# 800U-R3N3-Test.net
KiCad netlist of a schematic drawn in Altium Designer
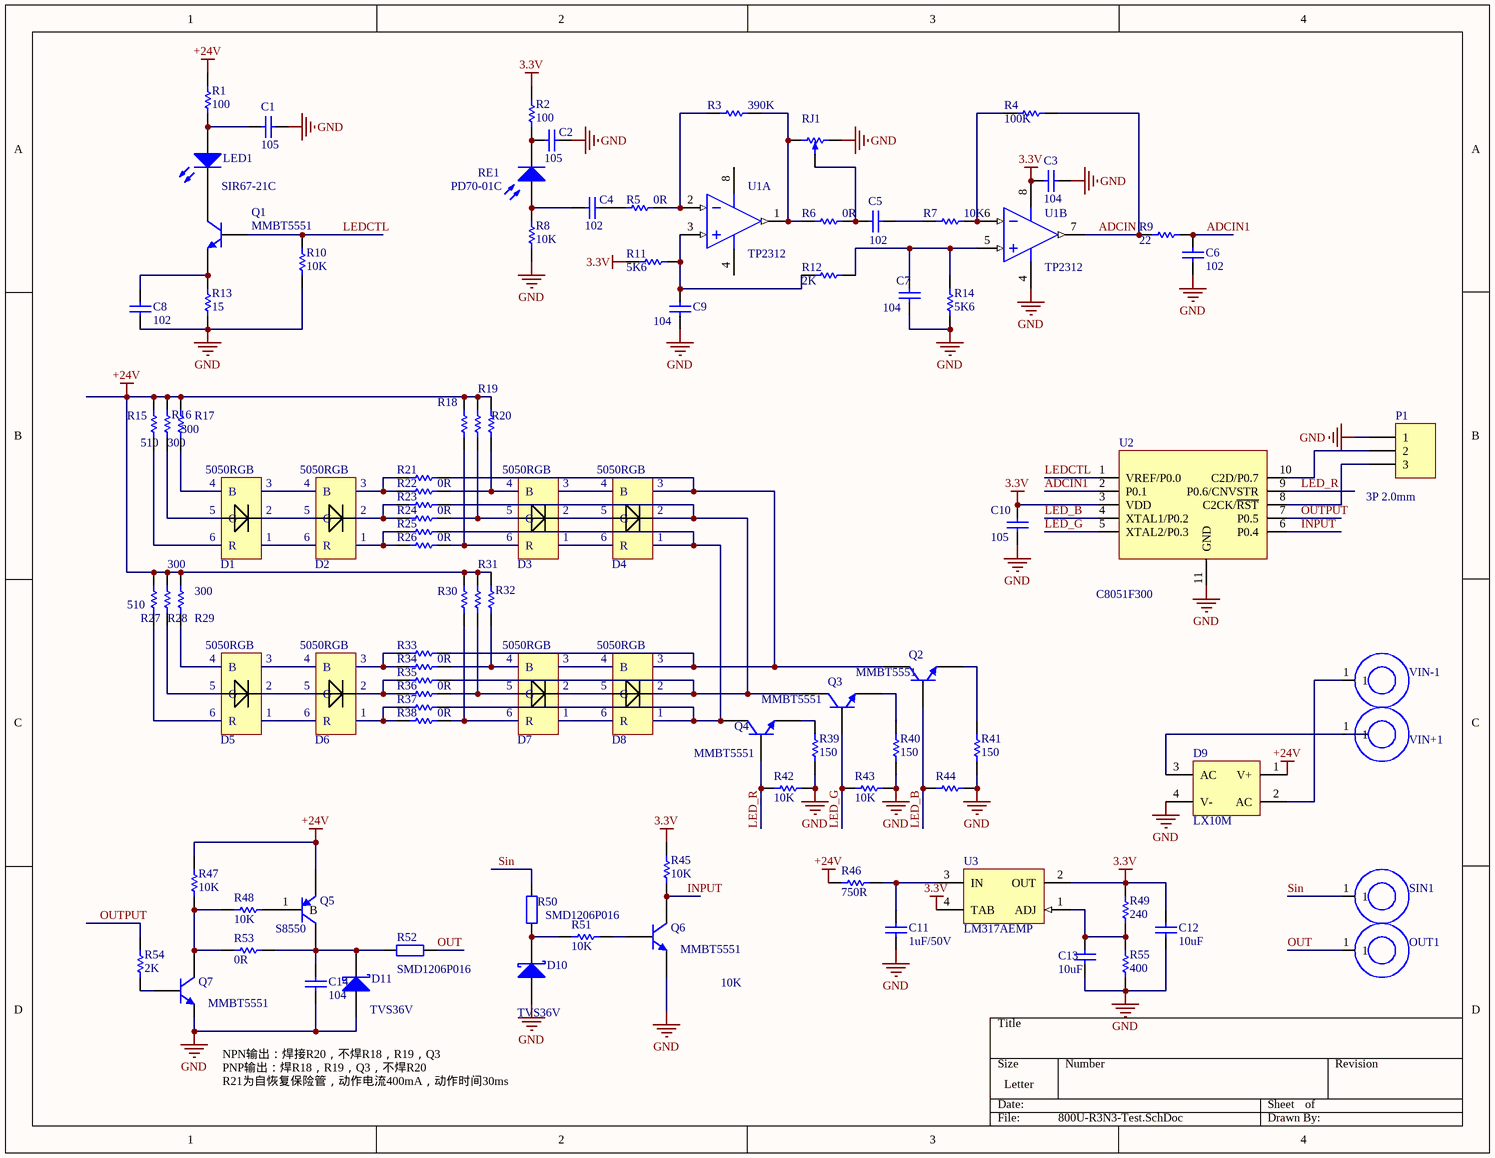
[diagram p0: 800U-R3N3-Test.SchDoc]

(export (version "E")
  (design (tool "Eeschema 10.0.6"))
  (components
    (comp (ref "C1")
      (value "105")
      (footprint "C0805")
      (description "贴片电容")
      (fields (field (name "PUBLISHER") "Altium Limited"))
      (libsource (lib "TMJD1.0") (part "Cap"))
    )
    (comp (ref "C2")
      (value "105")
      (footprint "C0603")
      (description "贴片电容")
      (fields (field (name "PUBLISHER") "Altium Limited"))
      (libsource (lib "TMJD1.0") (part "Cap"))
    )
    (comp (ref "C3")
      (value "104")
      (footprint "C0603")
      (description "贴片电容")
      (fields (field (name "PUBLISHER") "Altium Limited"))
      (libsource (lib "TMJD1.0") (part "Cap"))
    )
    (comp (ref "C4")
      (value "102")
      (footprint "C0603")
      (description "贴片电容")
      (fields (field (name "PUBLISHER") "Altium Limited"))
      (libsource (lib "TMJD1.0") (part "Cap"))
    )
    (comp (ref "C5")
      (value "102")
      (footprint "C0603")
      (description "贴片电容")
      (fields (field (name "PUBLISHER") "Altium Limited"))
      (libsource (lib "TMJD1.0") (part "Cap"))
    )
    (comp (ref "C6")
      (value "102")
      (footprint "C0603")
      (description "贴片电容")
      (fields (field (name "PUBLISHER") "Altium Limited"))
      (libsource (lib "TMJD1.0") (part "Cap"))
    )
    (comp (ref "C7")
      (value "104")
      (footprint "C0603")
      (description "贴片电容")
      (fields (field (name "PUBLISHER") "Altium Limited"))
      (libsource (lib "TMJD1.0") (part "Cap"))
    )
    (comp (ref "C8")
      (value "102")
      (footprint "C0603")
      (description "贴片电容")
      (fields (field (name "PUBLISHER") "Altium Limited"))
      (libsource (lib "TMJD1.0") (part "Cap"))
    )
    (comp (ref "C9")
      (value "104")
      (footprint "C0603")
      (description "贴片电容")
      (fields (field (name "PUBLISHER") "Altium Limited"))
      (libsource (lib "TMJD1.0") (part "Cap"))
    )
    (comp (ref "C10")
      (value "105")
      (footprint "C0603")
      (description "贴片电容")
      (fields (field (name "PUBLISHER") "Altium Limited"))
      (libsource (lib "TMJD1.0") (part "Cap"))
    )
    (comp (ref "C11")
      (value "1uF/50V")
      (footprint "C0603")
      (description "贴片电容")
      (fields (field (name "PUBLISHER") "Altium Limited"))
      (libsource (lib "Miscellaneous Devices") (part "Cap"))
    )
    (comp (ref "C12")
      (value "10uF")
      (footprint "C0603")
      (description "贴片电容")
      (fields (field (name "PUBLISHER") "Altium Limited"))
      (libsource (lib "Miscellaneous Devices") (part "Cap"))
    )
    (comp (ref "C13")
      (value "10uF")
      (footprint "C0603")
      (description "贴片电容")
      (fields (field (name "PUBLISHER") "Altium Limited"))
      (libsource (lib "Miscellaneous Devices") (part "Cap"))
    )
    (comp (ref "C14")
      (value "104")
      (footprint "C0603")
      (description "贴片电容")
      (fields (field (name "PUBLISHER") "Altium Limited"))
      (libsource (lib "TMJD1.0") (part "Cap"))
    )
    (comp (ref "D1")
      (value "5050RGB")
      (footprint "5050RGB")
      (description "贴片RBG发光管")
      (libsource (lib "MODBUS_V1.0") (part "5050RGB"))
    )
    (comp (ref "D2")
      (value "5050RGB")
      (footprint "5050RGB")
      (description "贴片RBG发光管")
      (libsource (lib "MODBUS_V1.0") (part "5050RGB"))
    )
    (comp (ref "D3")
      (value "5050RGB")
      (footprint "5050RGB")
      (description "贴片RBG发光管")
      (libsource (lib "MODBUS_V1.0") (part "5050RGB"))
    )
    (comp (ref "D4")
      (value "5050RGB")
      (footprint "5050RGB")
      (description "贴片RBG发光管")
      (libsource (lib "MODBUS_V1.0") (part "5050RGB"))
    )
    (comp (ref "D5")
      (value "5050RGB")
      (footprint "5050RGB")
      (description "贴片RBG发光管")
      (libsource (lib "MODBUS_V1.0") (part "5050RGB"))
    )
    (comp (ref "D6")
      (value "5050RGB")
      (footprint "5050RGB")
      (description "贴片RBG发光管")
      (libsource (lib "MODBUS_V1.0") (part "5050RGB"))
    )
    (comp (ref "D7")
      (value "5050RGB")
      (footprint "5050RGB")
      (description "贴片RBG发光管")
      (libsource (lib "MODBUS_V1.0") (part "5050RGB"))
    )
    (comp (ref "D8")
      (value "5050RGB")
      (footprint "5050RGB")
      (description "贴片RBG发光管")
      (libsource (lib "MODBUS_V1.0") (part "5050RGB"))
    )
    (comp (ref "D9")
      (value "LX10M")
      (footprint "桥堆 3.8*3.5")
      (description "贴片桥堆")
      (libsource (lib "Miscellaneous Devices") (part "Bridge2"))
    )
    (comp (ref "D10")
      (value "TVS36V")
      (footprint "D1206")
      (description "贴片TVS")
      (fields (field (name "PUBLISHER") "Altium Limited"))
      (libsource (lib "*") (part "D Schottky"))
    )
    (comp (ref "D11")
      (value "TVS36V")
      (footprint "D1206")
      (description "贴片TVS")
      (fields (field (name "PUBLISHER") "Altium Limited"))
      (libsource (lib "*") (part "D Schottky"))
    )
    (comp (ref "LED1")
      (value "SIR67-21C")
      (footprint "LED-3.5X2.8")
      (description "贴片红外发射管")
      (fields (field (name "PUBLISHER") "Altium Limited"))
      (libsource (lib "Miscellaneous Devices") (part "LED0"))
    )
    (comp (ref "OUT1") (value "~") (footprint "HOLE_SMD") (libsource (lib "910U_D24S") (part "HOLE")))
    (comp (ref "P1")
      (value "3P 2.0mm")
      (footprint "PIN3-2.0mm")
      (description "插座")
      (fields (field (name "PUBLISHER") "Altium Limited"))
      (libsource (lib "Miscellaneous Connectors") (part "MHDR1X3"))
    )
    (comp (ref "Q1")
      (value "MMBT5551")
      (footprint "SOT-23")
      (description "贴片NPN三极管")
      (libsource (lib "Miscellaneous Devices") (part "NPN"))
    )
    (comp (ref "Q2")
      (value "MMBT5551")
      (footprint "SOT-23")
      (description "贴片NPN三极管")
      (libsource (lib "Miscellaneous Devices") (part "NPN"))
    )
    (comp (ref "Q3")
      (value "MMBT5551")
      (footprint "SOT-23")
      (description "贴片NPN三极管")
      (libsource (lib "Miscellaneous Devices") (part "NPN"))
    )
    (comp (ref "Q4")
      (value "MMBT5551")
      (footprint "SOT-23")
      (description "贴片NPN三极管")
      (libsource (lib "Miscellaneous Devices") (part "NPN"))
    )
    (comp (ref "Q5")
      (value "S8550")
      (footprint "SOT-23")
      (description "贴片PNP三极管")
      (libsource (lib "MODBUS_V1.0") (part "S8550"))
    )
    (comp (ref "Q6")
      (value "MMBT5551")
      (footprint "SOT-23")
      (description "贴片NPN三极管")
      (libsource (lib "Miscellaneous Devices") (part "NPN"))
    )
    (comp (ref "Q7")
      (value "MMBT5551")
      (footprint "SOT-23")
      (description "NPN三极管")
      (fields (field (name "Comment") "贴片三极管"))
      (libsource (lib "Miscellaneous Devices") (part "NPN"))
    )
    (comp (ref "R1")
      (value "100")
      (footprint "R0805")
      (description "贴片电阻")
      (libsource (lib "Miscellaneous Devices") (part "Res Semi"))
    )
    (comp (ref "R2")
      (value "100")
      (footprint "R0603")
      (description "贴片电阻")
      (libsource (lib "Miscellaneous Devices") (part "Res Semi"))
    )
    (comp (ref "R3")
      (value "390K")
      (footprint "R0603")
      (description "贴片电阻")
      (libsource (lib "Miscellaneous Devices") (part "Res Semi"))
    )
    (comp (ref "R4")
      (value "100K")
      (footprint "R0603")
      (description "贴片电阻")
      (libsource (lib "Miscellaneous Devices") (part "Res Semi"))
    )
    (comp (ref "R5")
      (value "0R")
      (footprint "R0603")
      (description "贴片电阻")
      (libsource (lib "Miscellaneous Devices") (part "Res Semi"))
    )
    (comp (ref "R6")
      (value "0R")
      (footprint "R0603")
      (description "贴片电阻")
      (libsource (lib "Miscellaneous Devices") (part "Res Semi"))
    )
    (comp (ref "R7")
      (value "10K")
      (footprint "R0603")
      (description "贴片电阻")
      (libsource (lib "Miscellaneous Devices") (part "Res Semi"))
    )
    (comp (ref "R8")
      (value "10K")
      (footprint "R0603")
      (description "贴片电阻")
      (libsource (lib "Miscellaneous Devices") (part "Res Semi"))
    )
    (comp (ref "R9")
      (value "22")
      (footprint "R0603")
      (description "贴片电阻")
      (libsource (lib "Miscellaneous Devices") (part "Res Semi"))
    )
    (comp (ref "R10")
      (value "10K")
      (footprint "R0603")
      (description "贴片电阻")
      (libsource (lib "Miscellaneous Devices") (part "Res Semi"))
    )
    (comp (ref "R11")
      (value "5K6")
      (footprint "R0603")
      (description "贴片电阻")
      (libsource (lib "Miscellaneous Devices") (part "Res Semi"))
    )
    (comp (ref "R12")
      (value "2K")
      (footprint "R0603")
      (description "贴片电阻")
      (libsource (lib "Miscellaneous Devices") (part "Res Semi"))
    )
    (comp (ref "R13")
      (value "15")
      (footprint "R0805")
      (description "贴片电阻")
      (libsource (lib "Miscellaneous Devices") (part "Res Semi"))
    )
    (comp (ref "R14")
      (value "5K6")
      (footprint "R0603")
      (description "贴片电阻")
      (libsource (lib "Miscellaneous Devices") (part "Res Semi"))
    )
    (comp (ref "R15")
      (value "510")
      (footprint "2010")
      (description "贴片电阻")
      (libsource (lib "Miscellaneous Devices") (part "Res Semi"))
    )
    (comp (ref "R16")
      (value "300")
      (footprint "2010")
      (description "贴片电阻")
      (libsource (lib "Miscellaneous Devices") (part "Res Semi"))
    )
    (comp (ref "R17")
      (value "300")
      (footprint "2010")
      (description "贴片电阻")
      (libsource (lib "Miscellaneous Devices") (part "Res Semi"))
    )
    (comp (ref "R18")
      (value "~")
      (footprint "2010")
      (description "贴片电阻")
      (libsource (lib "Miscellaneous Devices") (part "Res Semi"))
    )
    (comp (ref "R19")
      (value "~")
      (footprint "2010")
      (description "贴片电阻")
      (libsource (lib "Miscellaneous Devices") (part "Res Semi"))
    )
    (comp (ref "R20")
      (value "~")
      (footprint "2010")
      (description "贴片电阻")
      (libsource (lib "Miscellaneous Devices") (part "Res Semi"))
    )
    (comp (ref "R21")
      (value "~")
      (footprint "R0603")
      (description "贴片电阻")
      (libsource (lib "Miscellaneous Devices") (part "Res Semi"))
    )
    (comp (ref "R22")
      (value "0R")
      (footprint "R0603")
      (description "贴片电阻")
      (libsource (lib "Miscellaneous Devices") (part "Res Semi"))
    )
    (comp (ref "R23")
      (value "~")
      (footprint "R0603")
      (description "贴片电阻")
      (libsource (lib "Miscellaneous Devices") (part "Res Semi"))
    )
    (comp (ref "R24")
      (value "0R")
      (footprint "R0603")
      (description "贴片电阻")
      (libsource (lib "Miscellaneous Devices") (part "Res Semi"))
    )
    (comp (ref "R25")
      (value "~")
      (footprint "R0603")
      (description "贴片电阻")
      (libsource (lib "Miscellaneous Devices") (part "Res Semi"))
    )
    (comp (ref "R26")
      (value "0R")
      (footprint "R0603")
      (description "贴片电阻")
      (libsource (lib "Miscellaneous Devices") (part "Res Semi"))
    )
    (comp (ref "R27")
      (value "510")
      (footprint "2010")
      (description "贴片电阻")
      (libsource (lib "Miscellaneous Devices") (part "Res Semi"))
    )
    (comp (ref "R28")
      (value "300")
      (footprint "2010")
      (description "贴片电阻")
      (libsource (lib "Miscellaneous Devices") (part "Res Semi"))
    )
    (comp (ref "R29")
      (value "300")
      (footprint "2010")
      (description "贴片电阻")
      (libsource (lib "Miscellaneous Devices") (part "Res Semi"))
    )
    (comp (ref "R30")
      (value "~")
      (footprint "2010")
      (description "贴片电阻")
      (libsource (lib "Miscellaneous Devices") (part "Res Semi"))
    )
    (comp (ref "R31")
      (value "~")
      (footprint "2010")
      (description "贴片电阻")
      (libsource (lib "Miscellaneous Devices") (part "Res Semi"))
    )
    (comp (ref "R32")
      (value "~")
      (footprint "2010")
      (description "贴片电阻")
      (libsource (lib "Miscellaneous Devices") (part "Res Semi"))
    )
    (comp (ref "R33")
      (value "~")
      (footprint "R0603")
      (description "贴片电阻")
      (libsource (lib "Miscellaneous Devices") (part "Res Semi"))
    )
    (comp (ref "R34")
      (value "0R")
      (footprint "R0603")
      (description "贴片电阻")
      (libsource (lib "Miscellaneous Devices") (part "Res Semi"))
    )
    (comp (ref "R35")
      (value "~")
      (footprint "R0603")
      (description "贴片电阻")
      (libsource (lib "Miscellaneous Devices") (part "Res Semi"))
    )
    (comp (ref "R36")
      (value "0R")
      (footprint "R0603")
      (description "贴片电阻")
      (libsource (lib "Miscellaneous Devices") (part "Res Semi"))
    )
    (comp (ref "R37")
      (value "~")
      (footprint "R0603")
      (description "贴片电阻")
      (libsource (lib "Miscellaneous Devices") (part "Res Semi"))
    )
    (comp (ref "R38")
      (value "0R")
      (footprint "R0603")
      (description "贴片电阻")
      (libsource (lib "Miscellaneous Devices") (part "Res Semi"))
    )
    (comp (ref "R39")
      (value "150")
      (footprint "2010")
      (description "贴片电阻")
      (libsource (lib "Miscellaneous Devices") (part "Res Semi"))
    )
    (comp (ref "R40")
      (value "150")
      (footprint "2010")
      (description "贴片电阻")
      (libsource (lib "Miscellaneous Devices") (part "Res Semi"))
    )
    (comp (ref "R41")
      (value "150")
      (footprint "2010")
      (description "贴片电阻")
      (libsource (lib "Miscellaneous Devices") (part "Res Semi"))
    )
    (comp (ref "R42")
      (value "10K")
      (footprint "R0603")
      (description "贴片电阻")
      (libsource (lib "Miscellaneous Devices") (part "Res Semi"))
    )
    (comp (ref "R43")
      (value "10K")
      (footprint "R0603")
      (description "贴片电阻")
      (libsource (lib "Miscellaneous Devices") (part "Res Semi"))
    )
    (comp (ref "R44")
      (value "10K")
      (footprint "R0603")
      (description "贴片电阻")
      (libsource (lib "Miscellaneous Devices") (part "Res Semi"))
    )
    (comp (ref "R45")
      (value "10K")
      (footprint "R0603")
      (description "贴片电阻")
      (libsource (lib "Miscellaneous Devices") (part "Res Semi"))
    )
    (comp (ref "R46")
      (value "750R")
      (footprint "2010")
      (description "贴片电阻")
      (libsource (lib "Miscellaneous Devices") (part "Res Semi"))
    )
    (comp (ref "R47")
      (value "10K")
      (footprint "R0603")
      (description "贴片电阻")
      (libsource (lib "Miscellaneous Devices") (part "Res Semi"))
    )
    (comp (ref "R48")
      (value "10K")
      (footprint "R0603")
      (description "贴片电阻")
      (libsource (lib "Miscellaneous Devices") (part "Res Semi"))
    )
    (comp (ref "R49")
      (value "240")
      (footprint "R0603")
      (description "贴片电阻")
      (libsource (lib "Miscellaneous Devices") (part "Res Semi"))
    )
    (comp (ref "R50")
      (value "SMD1206P016")
      (footprint "1206")
      (description "贴片过流保护")
      (fields (field (name "PUBLISHER") "Altium Limited"))
      (libsource (lib "Miscellaneous Devices") (part "Res2"))
    )
    (comp (ref "R51")
      (value "10K")
      (footprint "R0603")
      (description "贴片电阻")
      (libsource (lib "Miscellaneous Devices") (part "Res Semi"))
    )
    (comp (ref "R52")
      (value "SMD1206P016")
      (footprint "1206")
      (description "贴片过流保护")
      (fields (field (name "PUBLISHER") "Altium Limited"))
      (libsource (lib "") (part "Res2_1"))
    )
    (comp (ref "R53")
      (value "0R")
      (footprint "R0603")
      (description "贴片电阻")
      (libsource (lib "Miscellaneous Devices") (part "Res Semi"))
    )
    (comp (ref "R54")
      (value "2K")
      (footprint "R0603")
      (description "贴片电阻")
      (libsource (lib "Miscellaneous Devices") (part "Res Semi"))
    )
    (comp (ref "R55")
      (value "400")
      (footprint "R0603")
      (description "贴片电阻")
      (libsource (lib "Miscellaneous Devices") (part "Res Semi"))
    )
    (comp (ref "RE1")
      (value "PD70-01C")
      (footprint "LED-1210")
      (description "贴片接收管")
      (fields (field (name "PUBLISHER") "Altium Limited"))
      (libsource (lib "Miscellaneous Devices") (part "Photo Sen"))
    )
    (comp (ref "RJ1")
      (value "~")
      (footprint "POT4MM-2")
      (description "贴片可调电阻")
      (fields (field (name "PUBLISHER") "Altium Limited"))
      (libsource (lib "Miscellaneous Devices") (part "RPot SM"))
    )
    (comp (ref "SIN1") (value "~") (footprint "HOLE_SMD") (libsource (lib "910U_D24S") (part "HOLE")))
    (comp (ref "U1")
      (value "TP2312")
      (footprint "SO-8")
      (description "贴片芯片")
      (fields (field (name "PUBLISHER") "Altium Limited"))
      (libsource (lib "Motorola Amplifier Audio Amplifier") (part "LM833D"))
    )
    (comp (ref "U2")
      (value "C8051F300")
      (footprint "IC3-3-14P")
      (description "贴片芯片")
      (libsource (lib "集成块") (part "PIC16C505"))
    )
    (comp (ref "U3")
      (value "LM317AEMP")
      (footprint "MP04A_N")
      (description "贴片芯片")
      (fields
        (field (name "MANUFACTURER") "National Semiconductor")
        (field (name "DIGIKEYPARTNUMBER") "LM317AEMPCT-ND")
        (field (name "PUBLISHER") "Altium Limited")
      )
      (libsource (lib "NSC LDO") (part "LM317AEMP"))
    )
    (comp (ref "VIN+1") (value "~") (footprint "HOLE_SMD") (libsource (lib "910U_D24S") (part "HOLE")))
    (comp (ref "VIN-1") (value "~") (footprint "HOLE_SMD") (libsource (lib "910U_D24S") (part "HOLE")))
  )
  (nets
    (net (code "1") (name "+24V") (class "Default")
      (node (ref "D9") (pin "1") (pinfunction "V+_1") (pintype "passive"))
      (node (ref "Q5") (pin "2") (pinfunction "E_2") (pintype "passive"))
      (node (ref "R1") (pin "2") (pinfunction "2_2") (pintype "passive"))
      (node (ref "R15") (pin "1") (pinfunction "1_1") (pintype "passive"))
      (node (ref "R16") (pin "1") (pinfunction "1_1") (pintype "passive"))
      (node (ref "R17") (pin "1") (pinfunction "1_1") (pintype "passive"))
      (node (ref "R18") (pin "1") (pinfunction "1_1") (pintype "passive"))
      (node (ref "R19") (pin "1") (pinfunction "1_1") (pintype "passive"))
      (node (ref "R20") (pin "1") (pinfunction "1_1") (pintype "passive"))
      (node (ref "R27") (pin "1") (pinfunction "1_1") (pintype "passive"))
      (node (ref "R28") (pin "1") (pinfunction "1_1") (pintype "passive"))
      (node (ref "R29") (pin "1") (pinfunction "1_1") (pintype "passive"))
      (node (ref "R30") (pin "1") (pinfunction "1_1") (pintype "passive"))
      (node (ref "R31") (pin "1") (pinfunction "1_1") (pintype "passive"))
      (node (ref "R32") (pin "1") (pinfunction "1_1") (pintype "passive"))
      (node (ref "R46") (pin "1") (pinfunction "1_1") (pintype "passive"))
      (node (ref "R47") (pin "2") (pinfunction "2_2") (pintype "passive"))
    )
    (net (code "2") (name "/ADCIN") (class "Default")
      (node (ref "R4") (pin "2") (pinfunction "2_2") (pintype "passive"))
      (node (ref "R9") (pin "1") (pinfunction "1_1") (pintype "passive"))
      (node (ref "U1") (pin "7") (pinfunction "OUT_7") (pintype "output"))
    )
    (net (code "3") (name "/ADCIN1") (class "Default")
      (node (ref "C6") (pin "2") (pinfunction "2_2") (pintype "passive"))
      (node (ref "R9") (pin "2") (pinfunction "2_2") (pintype "passive"))
      (node (ref "U2") (pin "2") (pinfunction "P0.1_2") (pintype "passive"))
    )
    (net (code "4") (name "/INPUT") (class "Default")
      (node (ref "Q6") (pin "3") (pinfunction "C_3") (pintype "passive"))
      (node (ref "R45") (pin "1") (pinfunction "1_1") (pintype "passive"))
      (node (ref "U2") (pin "6") (pinfunction "P0.4_6") (pintype "passive"))
    )
    (net (code "5") (name "/LEDCTL") (class "Default")
      (node (ref "Q1") (pin "1") (pinfunction "B_1") (pintype "passive"))
      (node (ref "R10") (pin "2") (pinfunction "2_2") (pintype "passive"))
      (node (ref "U2") (pin "1") (pinfunction "VREF/P0.0_1") (pintype "passive"))
    )
    (net (code "6") (name "/LED_B") (class "Default")
      (node (ref "Q2") (pin "1") (pinfunction "B_1") (pintype "passive"))
      (node (ref "R44") (pin "1") (pinfunction "1_1") (pintype "passive"))
      (node (ref "U2") (pin "4") (pinfunction "XTAL1/P0.2_4") (pintype "passive"))
    )
    (net (code "7") (name "/LED_G") (class "Default")
      (node (ref "Q3") (pin "1") (pinfunction "B_1") (pintype "passive"))
      (node (ref "R43") (pin "1") (pinfunction "1_1") (pintype "passive"))
      (node (ref "U2") (pin "5") (pinfunction "XTAL2/P0.3_5") (pintype "passive"))
    )
    (net (code "8") (name "/LED_R") (class "Default")
      (node (ref "Q4") (pin "1") (pinfunction "B_1") (pintype "passive"))
      (node (ref "R42") (pin "1") (pinfunction "1_1") (pintype "passive"))
      (node (ref "U2") (pin "9") (pinfunction "P0.6/CNVSTR_9") (pintype "passive"))
    )
    (net (code "9") (name "/OUT") (class "Default")
      (node (ref "OUT1") (pin "1") (pinfunction "1_1") (pintype "passive"))
      (node (ref "R52") (pin "2") (pinfunction "2_2") (pintype "passive"))
    )
    (net (code "10") (name "/OUTPUT") (class "Default")
      (node (ref "R54") (pin "2") (pinfunction "2_2") (pintype "passive"))
      (node (ref "U2") (pin "7") (pinfunction "P0.5_7") (pintype "passive"))
    )
    (net (code "11") (name "/Sin") (class "Default")
      (node (ref "R50") (pin "2") (pinfunction "2_2") (pintype "passive"))
      (node (ref "SIN1") (pin "1") (pinfunction "1_1") (pintype "passive"))
    )
    (net (code "12") (name "3.3V") (class "Default")
      (node (ref "C10") (pin "1") (pinfunction "1_1") (pintype "passive"))
      (node (ref "C12") (pin "1") (pinfunction "1_1") (pintype "passive"))
      (node (ref "C3") (pin "1") (pinfunction "1_1") (pintype "passive"))
      (node (ref "R11") (pin "1") (pinfunction "1_1") (pintype "passive"))
      (node (ref "R2") (pin "2") (pinfunction "2_2") (pintype "passive"))
      (node (ref "R45") (pin "2") (pinfunction "2_2") (pintype "passive"))
      (node (ref "R49") (pin "2") (pinfunction "2_2") (pintype "passive"))
      (node (ref "U1") (pin "8") (pinfunction "VCC_8") (pintype "power_in"))
      (node (ref "U2") (pin "3") (pinfunction "VDD_3") (pintype "passive"))
      (node (ref "U3") (pin "2") (pinfunction "OUT_2") (pintype "power_in"))
      (node (ref "U3") (pin "4") (pinfunction "TAB_4") (pintype "power_in"))
    )
    (net (code "13") (name "GND") (class "Default")
      (node (ref "C1") (pin "2") (pinfunction "2_2") (pintype "passive"))
      (node (ref "C10") (pin "2") (pinfunction "2_2") (pintype "passive"))
      (node (ref "C11") (pin "2") (pinfunction "2_2") (pintype "passive"))
      (node (ref "C12") (pin "2") (pinfunction "2_2") (pintype "passive"))
      (node (ref "C13") (pin "2") (pinfunction "2_2") (pintype "passive"))
      (node (ref "C14") (pin "2") (pinfunction "2_2") (pintype "passive"))
      (node (ref "C2") (pin "2") (pinfunction "2_2") (pintype "passive"))
      (node (ref "C3") (pin "2") (pinfunction "2_2") (pintype "passive"))
      (node (ref "C6") (pin "1") (pinfunction "1_1") (pintype "passive"))
      (node (ref "C7") (pin "2") (pinfunction "2_2") (pintype "passive"))
      (node (ref "C8") (pin "2") (pinfunction "2_2") (pintype "passive"))
      (node (ref "C9") (pin "2") (pinfunction "2_2") (pintype "passive"))
      (node (ref "D10") (pin "1") (pinfunction "A_1") (pintype "passive"))
      (node (ref "D11") (pin "1") (pinfunction "A_1") (pintype "passive"))
      (node (ref "D9") (pin "4") (pinfunction "V-_4") (pintype "passive"))
      (node (ref "P1") (pin "1") (pinfunction "1_1") (pintype "passive"))
      (node (ref "Q6") (pin "2") (pinfunction "E_2") (pintype "passive"))
      (node (ref "Q7") (pin "2") (pinfunction "E_2") (pintype "passive"))
      (node (ref "R10") (pin "1") (pinfunction "1_1") (pintype "passive"))
      (node (ref "R13") (pin "1") (pinfunction "1_1") (pintype "passive"))
      (node (ref "R14") (pin "1") (pinfunction "1_1") (pintype "passive"))
      (node (ref "R39") (pin "2") (pinfunction "2_2") (pintype "passive"))
      (node (ref "R40") (pin "2") (pinfunction "2_2") (pintype "passive"))
      (node (ref "R41") (pin "2") (pinfunction "2_2") (pintype "passive"))
      (node (ref "R42") (pin "2") (pinfunction "2_2") (pintype "passive"))
      (node (ref "R43") (pin "2") (pinfunction "2_2") (pintype "passive"))
      (node (ref "R44") (pin "2") (pinfunction "2_2") (pintype "passive"))
      (node (ref "R55") (pin "1") (pinfunction "1_1") (pintype "passive"))
      (node (ref "R8") (pin "1") (pinfunction "1_1") (pintype "passive"))
      (node (ref "RJ1") (pin "CW") (pinfunction "+_CW") (pintype "passive"))
      (node (ref "U1") (pin "4") (pinfunction "VEE_4") (pintype "power_in"))
      (node (ref "U2") (pin "11") (pinfunction "GND_11") (pintype "passive"))
    )
    (net (code "14") (name "Net-(C4-Pad2)") (class "Default")
      (node (ref "C4") (pin "2") (pinfunction "2_2") (pintype "passive"))
      (node (ref "R5") (pin "1") (pinfunction "1_1") (pintype "passive"))
    )
    (net (code "15") (name "Net-(C5-Pad1)") (class "Default")
      (node (ref "C5") (pin "1") (pinfunction "1_1") (pintype "passive"))
      (node (ref "R6") (pin "2") (pinfunction "2_2") (pintype "passive"))
      (node (ref "RJ1") (pin "W") (pinfunction "W_W") (pintype "passive"))
    )
    (net (code "16") (name "Net-(C5-Pad2)") (class "Default")
      (node (ref "C5") (pin "2") (pinfunction "2_2") (pintype "passive"))
      (node (ref "R7") (pin "1") (pinfunction "1_1") (pintype "passive"))
    )
    (net (code "17") (name "Net-(D1-B)") (class "Default")
      (node (ref "D1") (pin "4") (pinfunction "B_4") (pintype "passive"))
      (node (ref "R17") (pin "2") (pinfunction "2_2") (pintype "passive"))
    )
    (net (code "18") (name "Net-(D1-G)") (class "Default")
      (node (ref "D1") (pin "5") (pinfunction "G_5") (pintype "passive"))
      (node (ref "R16") (pin "2") (pinfunction "2_2") (pintype "passive"))
    )
    (net (code "19") (name "Net-(D1-R)") (class "Default")
      (node (ref "D1") (pin "6") (pinfunction "R_6") (pintype "passive"))
      (node (ref "R15") (pin "2") (pinfunction "2_2") (pintype "passive"))
    )
    (net (code "20") (name "Net-(D2-B)") (class "Default")
      (node (ref "D1") (pin "3") (pintype "passive"))
      (node (ref "D2") (pin "4") (pinfunction "B_4") (pintype "passive"))
    )
    (net (code "21") (name "Net-(D2-G)") (class "Default")
      (node (ref "D1") (pin "2") (pintype "passive"))
      (node (ref "D2") (pin "5") (pinfunction "G_5") (pintype "passive"))
    )
    (net (code "22") (name "Net-(D2-Pad1)") (class "Default")
      (node (ref "D2") (pin "1") (pintype "passive"))
      (node (ref "R25") (pin "1") (pinfunction "1_1") (pintype "passive"))
      (node (ref "R26") (pin "1") (pinfunction "1_1") (pintype "passive"))
    )
    (net (code "23") (name "Net-(D2-Pad2)") (class "Default")
      (node (ref "D2") (pin "2") (pintype "passive"))
      (node (ref "R23") (pin "1") (pinfunction "1_1") (pintype "passive"))
      (node (ref "R24") (pin "1") (pinfunction "1_1") (pintype "passive"))
    )
    (net (code "24") (name "Net-(D2-Pad3)") (class "Default")
      (node (ref "D2") (pin "3") (pintype "passive"))
      (node (ref "R21") (pin "1") (pinfunction "1_1") (pintype "passive"))
      (node (ref "R22") (pin "1") (pinfunction "1_1") (pintype "passive"))
    )
    (net (code "25") (name "Net-(D2-R)") (class "Default")
      (node (ref "D1") (pin "1") (pintype "passive"))
      (node (ref "D2") (pin "6") (pinfunction "R_6") (pintype "passive"))
    )
    (net (code "26") (name "Net-(D3-B)") (class "Default")
      (node (ref "D3") (pin "4") (pinfunction "B_4") (pintype "passive"))
      (node (ref "R20") (pin "2") (pinfunction "2_2") (pintype "passive"))
      (node (ref "R22") (pin "2") (pinfunction "2_2") (pintype "passive"))
    )
    (net (code "27") (name "Net-(D3-G)") (class "Default")
      (node (ref "D3") (pin "5") (pinfunction "G_5") (pintype "passive"))
      (node (ref "R19") (pin "2") (pinfunction "2_2") (pintype "passive"))
      (node (ref "R24") (pin "2") (pinfunction "2_2") (pintype "passive"))
    )
    (net (code "28") (name "Net-(D3-R)") (class "Default")
      (node (ref "D3") (pin "6") (pinfunction "R_6") (pintype "passive"))
      (node (ref "R18") (pin "2") (pinfunction "2_2") (pintype "passive"))
      (node (ref "R26") (pin "2") (pinfunction "2_2") (pintype "passive"))
    )
    (net (code "29") (name "Net-(D4-B)") (class "Default")
      (node (ref "D3") (pin "3") (pintype "passive"))
      (node (ref "D4") (pin "4") (pinfunction "B_4") (pintype "passive"))
    )
    (net (code "30") (name "Net-(D4-G)") (class "Default")
      (node (ref "D3") (pin "2") (pintype "passive"))
      (node (ref "D4") (pin "5") (pinfunction "G_5") (pintype "passive"))
    )
    (net (code "31") (name "Net-(D4-R)") (class "Default")
      (node (ref "D3") (pin "1") (pintype "passive"))
      (node (ref "D4") (pin "6") (pinfunction "R_6") (pintype "passive"))
    )
    (net (code "32") (name "Net-(D5-B)") (class "Default")
      (node (ref "D5") (pin "4") (pinfunction "B_4") (pintype "passive"))
      (node (ref "R29") (pin "2") (pinfunction "2_2") (pintype "passive"))
    )
    (net (code "33") (name "Net-(D5-G)") (class "Default")
      (node (ref "D5") (pin "5") (pinfunction "G_5") (pintype "passive"))
      (node (ref "R28") (pin "2") (pinfunction "2_2") (pintype "passive"))
    )
    (net (code "34") (name "Net-(D5-R)") (class "Default")
      (node (ref "D5") (pin "6") (pinfunction "R_6") (pintype "passive"))
      (node (ref "R27") (pin "2") (pinfunction "2_2") (pintype "passive"))
    )
    (net (code "35") (name "Net-(D6-B)") (class "Default")
      (node (ref "D5") (pin "3") (pintype "passive"))
      (node (ref "D6") (pin "4") (pinfunction "B_4") (pintype "passive"))
    )
    (net (code "36") (name "Net-(D6-G)") (class "Default")
      (node (ref "D5") (pin "2") (pintype "passive"))
      (node (ref "D6") (pin "5") (pinfunction "G_5") (pintype "passive"))
    )
    (net (code "37") (name "Net-(D6-Pad1)") (class "Default")
      (node (ref "D6") (pin "1") (pintype "passive"))
      (node (ref "R37") (pin "1") (pinfunction "1_1") (pintype "passive"))
      (node (ref "R38") (pin "1") (pinfunction "1_1") (pintype "passive"))
    )
    (net (code "38") (name "Net-(D6-Pad2)") (class "Default")
      (node (ref "D6") (pin "2") (pintype "passive"))
      (node (ref "R35") (pin "1") (pinfunction "1_1") (pintype "passive"))
      (node (ref "R36") (pin "1") (pinfunction "1_1") (pintype "passive"))
    )
    (net (code "39") (name "Net-(D6-Pad3)") (class "Default")
      (node (ref "D6") (pin "3") (pintype "passive"))
      (node (ref "R33") (pin "1") (pinfunction "1_1") (pintype "passive"))
      (node (ref "R34") (pin "1") (pinfunction "1_1") (pintype "passive"))
    )
    (net (code "40") (name "Net-(D6-R)") (class "Default")
      (node (ref "D5") (pin "1") (pintype "passive"))
      (node (ref "D6") (pin "6") (pinfunction "R_6") (pintype "passive"))
    )
    (net (code "41") (name "Net-(D7-B)") (class "Default")
      (node (ref "D7") (pin "4") (pinfunction "B_4") (pintype "passive"))
      (node (ref "R32") (pin "2") (pinfunction "2_2") (pintype "passive"))
      (node (ref "R34") (pin "2") (pinfunction "2_2") (pintype "passive"))
    )
    (net (code "42") (name "Net-(D7-G)") (class "Default")
      (node (ref "D7") (pin "5") (pinfunction "G_5") (pintype "passive"))
      (node (ref "R31") (pin "2") (pinfunction "2_2") (pintype "passive"))
      (node (ref "R36") (pin "2") (pinfunction "2_2") (pintype "passive"))
    )
    (net (code "43") (name "Net-(D7-R)") (class "Default")
      (node (ref "D7") (pin "6") (pinfunction "R_6") (pintype "passive"))
      (node (ref "R30") (pin "2") (pinfunction "2_2") (pintype "passive"))
      (node (ref "R38") (pin "2") (pinfunction "2_2") (pintype "passive"))
    )
    (net (code "44") (name "Net-(D8-B)") (class "Default")
      (node (ref "D7") (pin "3") (pintype "passive"))
      (node (ref "D8") (pin "4") (pinfunction "B_4") (pintype "passive"))
    )
    (net (code "45") (name "Net-(D8-G)") (class "Default")
      (node (ref "D7") (pin "2") (pintype "passive"))
      (node (ref "D8") (pin "5") (pinfunction "G_5") (pintype "passive"))
    )
    (net (code "46") (name "Net-(D8-R)") (class "Default")
      (node (ref "D7") (pin "1") (pintype "passive"))
      (node (ref "D8") (pin "6") (pinfunction "R_6") (pintype "passive"))
    )
    (net (code "47") (name "Net-(D9-AC-Pad2)") (class "Default")
      (node (ref "D9") (pin "2") (pinfunction "AC_2") (pintype "passive"))
      (node (ref "VIN-1") (pin "1") (pinfunction "1_1") (pintype "passive"))
    )
    (net (code "48") (name "Net-(D9-AC-Pad3)") (class "Default")
      (node (ref "D9") (pin "3") (pinfunction "AC_3") (pintype "passive"))
      (node (ref "VIN+1") (pin "1") (pinfunction "1_1") (pintype "passive"))
    )
    (net (code "49") (name "Net-(D10-K)") (class "Default")
      (node (ref "D10") (pin "2") (pinfunction "K_2") (pintype "passive"))
      (node (ref "R50") (pin "1") (pinfunction "1_1") (pintype "passive"))
      (node (ref "R51") (pin "1") (pinfunction "1_1") (pintype "passive"))
    )
    (net (code "50") (name "Net-(D11-K)") (class "Default")
      (node (ref "C14") (pin "1") (pinfunction "1_1") (pintype "passive"))
      (node (ref "D11") (pin "2") (pinfunction "K_2") (pintype "passive"))
      (node (ref "Q5") (pin "3") (pinfunction "C_3") (pintype "passive"))
      (node (ref "R52") (pin "1") (pinfunction "1_1") (pintype "passive"))
      (node (ref "R53") (pin "2") (pinfunction "2_2") (pintype "passive"))
    )
    (net (code "51") (name "Net-(LED1-A)") (class "Default")
      (node (ref "C1") (pin "1") (pinfunction "1_1") (pintype "passive"))
      (node (ref "LED1") (pin "1") (pinfunction "A_1") (pintype "passive"))
      (node (ref "R1") (pin "1") (pinfunction "1_1") (pintype "passive"))
    )
    (net (code "52") (name "Net-(LED1-K)") (class "Default")
      (node (ref "LED1") (pin "2") (pinfunction "K_2") (pintype "passive"))
      (node (ref "Q1") (pin "3") (pinfunction "C_3") (pintype "passive"))
    )
    (net (code "53") (name "Net-(Q1-E)") (class "Default")
      (node (ref "C8") (pin "1") (pinfunction "1_1") (pintype "passive"))
      (node (ref "Q1") (pin "2") (pinfunction "E_2") (pintype "passive"))
      (node (ref "R13") (pin "2") (pinfunction "2_2") (pintype "passive"))
    )
    (net (code "54") (name "Net-(Q2-C)") (class "Default")
      (node (ref "D4") (pin "3") (pintype "passive"))
      (node (ref "D8") (pin "3") (pintype "passive"))
      (node (ref "Q2") (pin "3") (pinfunction "C_3") (pintype "passive"))
      (node (ref "R21") (pin "2") (pinfunction "2_2") (pintype "passive"))
      (node (ref "R33") (pin "2") (pinfunction "2_2") (pintype "passive"))
    )
    (net (code "55") (name "Net-(Q2-E)") (class "Default")
      (node (ref "Q2") (pin "2") (pinfunction "E_2") (pintype "passive"))
      (node (ref "R41") (pin "1") (pinfunction "1_1") (pintype "passive"))
    )
    (net (code "56") (name "Net-(Q3-C)") (class "Default")
      (node (ref "D4") (pin "2") (pintype "passive"))
      (node (ref "D8") (pin "2") (pintype "passive"))
      (node (ref "Q3") (pin "3") (pinfunction "C_3") (pintype "passive"))
      (node (ref "R23") (pin "2") (pinfunction "2_2") (pintype "passive"))
      (node (ref "R35") (pin "2") (pinfunction "2_2") (pintype "passive"))
    )
    (net (code "57") (name "Net-(Q3-E)") (class "Default")
      (node (ref "Q3") (pin "2") (pinfunction "E_2") (pintype "passive"))
      (node (ref "R40") (pin "1") (pinfunction "1_1") (pintype "passive"))
    )
    (net (code "58") (name "Net-(Q4-C)") (class "Default")
      (node (ref "D4") (pin "1") (pintype "passive"))
      (node (ref "D8") (pin "1") (pintype "passive"))
      (node (ref "Q4") (pin "3") (pinfunction "C_3") (pintype "passive"))
      (node (ref "R25") (pin "2") (pinfunction "2_2") (pintype "passive"))
      (node (ref "R37") (pin "2") (pinfunction "2_2") (pintype "passive"))
    )
    (net (code "59") (name "Net-(Q4-E)") (class "Default")
      (node (ref "Q4") (pin "2") (pinfunction "E_2") (pintype "passive"))
      (node (ref "R39") (pin "1") (pinfunction "1_1") (pintype "passive"))
    )
    (net (code "60") (name "Net-(Q5-B)") (class "Default")
      (node (ref "Q5") (pin "1") (pinfunction "B_1") (pintype "passive"))
      (node (ref "R48") (pin "2") (pinfunction "2_2") (pintype "passive"))
    )
    (net (code "61") (name "Net-(Q6-B)") (class "Default")
      (node (ref "Q6") (pin "1") (pinfunction "B_1") (pintype "passive"))
      (node (ref "R51") (pin "2") (pinfunction "2_2") (pintype "passive"))
    )
    (net (code "62") (name "Net-(Q7-B)") (class "Default")
      (node (ref "Q7") (pin "1") (pinfunction "B_1") (pintype "passive"))
      (node (ref "R54") (pin "1") (pinfunction "1_1") (pintype "passive"))
    )
    (net (code "63") (name "Net-(Q7-C)") (class "Default")
      (node (ref "Q7") (pin "3") (pinfunction "C_3") (pintype "passive"))
      (node (ref "R47") (pin "1") (pinfunction "1_1") (pintype "passive"))
      (node (ref "R48") (pin "1") (pinfunction "1_1") (pintype "passive"))
      (node (ref "R53") (pin "1") (pinfunction "1_1") (pintype "passive"))
    )
    (net (code "64") (name "Net-(RE1-A)") (class "Default")
      (node (ref "C4") (pin "1") (pinfunction "1_1") (pintype "passive"))
      (node (ref "R8") (pin "2") (pinfunction "2_2") (pintype "passive"))
      (node (ref "RE1") (pin "1") (pinfunction "A_1") (pintype "passive"))
    )
    (net (code "65") (name "Net-(RE1-K)") (class "Default")
      (node (ref "C2") (pin "1") (pinfunction "1_1") (pintype "passive"))
      (node (ref "R2") (pin "1") (pinfunction "1_1") (pintype "passive"))
      (node (ref "RE1") (pin "2") (pinfunction "K_2") (pintype "passive"))
    )
    (net (code "66") (name "Net-(RJ1--)") (class "Default")
      (node (ref "R3") (pin "2") (pinfunction "2_2") (pintype "passive"))
      (node (ref "R6") (pin "1") (pinfunction "1_1") (pintype "passive"))
      (node (ref "RJ1") (pin "CCW") (pinfunction "-_CCW") (pintype "passive"))
      (node (ref "U1") (pin "1") (pinfunction "OUT_1") (pintype "output"))
    )
    (net (code "67") (name "Net-(U1A-IN+)") (class "Default")
      (node (ref "C9") (pin "1") (pinfunction "1_1") (pintype "passive"))
      (node (ref "R11") (pin "2") (pinfunction "2_2") (pintype "passive"))
      (node (ref "R12") (pin "1") (pinfunction "1_1") (pintype "passive"))
      (node (ref "U1") (pin "3") (pinfunction "IN+_3") (pintype "input"))
    )
    (net (code "68") (name "Net-(U1A-IN-)") (class "Default")
      (node (ref "R3") (pin "1") (pinfunction "1_1") (pintype "passive"))
      (node (ref "R5") (pin "2") (pinfunction "2_2") (pintype "passive"))
      (node (ref "U1") (pin "2") (pinfunction "IN-_2") (pintype "input"))
    )
    (net (code "69") (name "Net-(U1B-IN+)") (class "Default")
      (node (ref "C7") (pin "1") (pinfunction "1_1") (pintype "passive"))
      (node (ref "R12") (pin "2") (pinfunction "2_2") (pintype "passive"))
      (node (ref "R14") (pin "2") (pinfunction "2_2") (pintype "passive"))
      (node (ref "U1") (pin "5") (pinfunction "IN+_5") (pintype "input"))
    )
    (net (code "70") (name "Net-(U1B-IN-)") (class "Default")
      (node (ref "R4") (pin "1") (pinfunction "1_1") (pintype "passive"))
      (node (ref "R7") (pin "2") (pinfunction "2_2") (pintype "passive"))
      (node (ref "U1") (pin "6") (pinfunction "IN-_6") (pintype "input"))
    )
    (net (code "71") (name "Net-(U2-C2CK{slash}~{RST})") (class "Default")
      (node (ref "P1") (pin "3") (pinfunction "3_3") (pintype "passive"))
      (node (ref "U2") (pin "8") (pinfunction "C2CK/~{RST}_8") (pintype "passive"))
    )
    (net (code "72") (name "Net-(U2-C2D{slash}P0.7)") (class "Default")
      (node (ref "P1") (pin "2") (pinfunction "2_2") (pintype "passive"))
      (node (ref "U2") (pin "10") (pinfunction "C2D/P0.7_10") (pintype "passive"))
    )
    (net (code "73") (name "Net-(U3-ADJ)") (class "Default")
      (node (ref "C13") (pin "1") (pinfunction "1_1") (pintype "passive"))
      (node (ref "R49") (pin "1") (pinfunction "1_1") (pintype "passive"))
      (node (ref "R55") (pin "2") (pinfunction "2_2") (pintype "passive"))
      (node (ref "U3") (pin "1") (pinfunction "ADJ_1") (pintype "input"))
    )
    (net (code "74") (name "Net-(U3-IN)") (class "Default")
      (node (ref "C11") (pin "1") (pinfunction "1_1") (pintype "passive"))
      (node (ref "R46") (pin "2") (pinfunction "2_2") (pintype "passive"))
      (node (ref "U3") (pin "3") (pinfunction "IN_3") (pintype "power_in"))
    )
    (net (code "75") (name "unconnected-(U1A-VCC-Pad8)") (class "Default")
      (node (ref "U1") (pin "8") (pinfunction "VCC_8") (pintype "power_in"))
    )
    (net (code "76") (name "unconnected-(U1A-VEE-Pad4)") (class "Default")
      (node (ref "U1") (pin "4") (pinfunction "VEE_4") (pintype "power_in"))
    )
  )
)
